# electrical_schematic.net
KiCad netlist of a schematic drawn in EAGLE
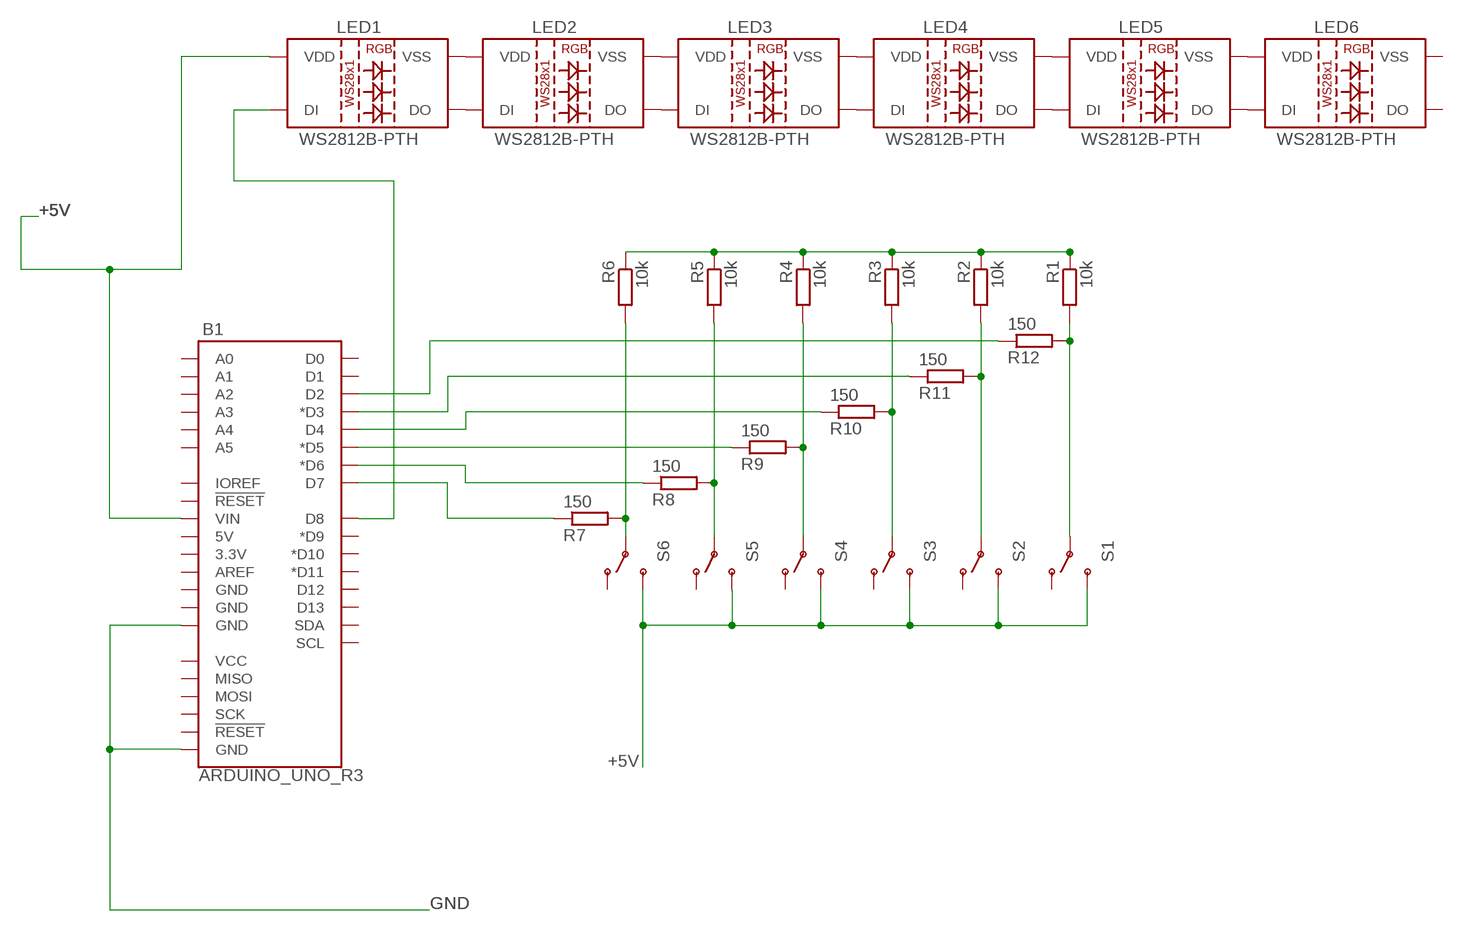
[diagram p0: schematic, sheet 1]

(export (version "E")
  (design (tool "Eeschema 10.0.6"))
  (components
    (comp (ref "B1")
      (value "ARDUINO_UNO_R3")
      (footprint "eagle-import:ARDUINO_R3")
      (libsource (lib "eagle-import") (part "ARDUINO_UNO_R3"))
    )
    (comp (ref "LED1")
      (value "WS2812B-PTH")
      (footprint "eagle-import:WS2812B-PTH-KIT")
      (libsource (lib "eagle-import") (part "WS2812B-PTH"))
    )
    (comp (ref "LED2")
      (value "WS2812B-PTH")
      (footprint "eagle-import:WS2812B-PTH-KIT")
      (libsource (lib "eagle-import") (part "WS2812B-PTH"))
    )
    (comp (ref "LED3")
      (value "WS2812B-PTH")
      (footprint "eagle-import:WS2812B-PTH-KIT")
      (libsource (lib "eagle-import") (part "WS2812B-PTH"))
    )
    (comp (ref "LED4")
      (value "WS2812B-PTH")
      (footprint "eagle-import:WS2812B-PTH-KIT")
      (libsource (lib "eagle-import") (part "WS2812B-PTH"))
    )
    (comp (ref "LED5")
      (value "WS2812B-PTH")
      (footprint "eagle-import:WS2812B-PTH-KIT")
      (libsource (lib "eagle-import") (part "WS2812B-PTH"))
    )
    (comp (ref "LED6")
      (value "WS2812B-PTH")
      (footprint "eagle-import:WS2812B-PTH-KIT")
      (libsource (lib "eagle-import") (part "WS2812B-PTH"))
    )
    (comp (ref "R1")
      (value "10k")
      (footprint "eagle-import:0207_12")
      (libsource (lib "eagle-import") (part "R-EU_0207/12"))
    )
    (comp (ref "R2")
      (value "10k")
      (footprint "eagle-import:0207_12")
      (libsource (lib "eagle-import") (part "R-EU_0207/12"))
    )
    (comp (ref "R3")
      (value "10k")
      (footprint "eagle-import:0207_12")
      (libsource (lib "eagle-import") (part "R-EU_0207/12"))
    )
    (comp (ref "R4")
      (value "10k")
      (footprint "eagle-import:0207_12")
      (libsource (lib "eagle-import") (part "R-EU_0207/12"))
    )
    (comp (ref "R5")
      (value "10k")
      (footprint "eagle-import:0207_12")
      (libsource (lib "eagle-import") (part "R-EU_0207/12"))
    )
    (comp (ref "R6")
      (value "10k")
      (footprint "eagle-import:0207_12")
      (libsource (lib "eagle-import") (part "R-EU_0207/12"))
    )
    (comp (ref "R7")
      (value "150")
      (footprint "eagle-import:0207_12")
      (libsource (lib "eagle-import") (part "R-EU_0207/12"))
    )
    (comp (ref "R8")
      (value "150")
      (footprint "eagle-import:0207_12")
      (libsource (lib "eagle-import") (part "R-EU_0207/12"))
    )
    (comp (ref "R9")
      (value "150")
      (footprint "eagle-import:0207_12")
      (libsource (lib "eagle-import") (part "R-EU_0207/12"))
    )
    (comp (ref "R10")
      (value "150")
      (footprint "eagle-import:0207_12")
      (libsource (lib "eagle-import") (part "R-EU_0207/12"))
    )
    (comp (ref "R11")
      (value "150")
      (footprint "eagle-import:0207_12")
      (libsource (lib "eagle-import") (part "R-EU_0207/12"))
    )
    (comp (ref "R12")
      (value "150")
      (footprint "eagle-import:0207_12")
      (libsource (lib "eagle-import") (part "R-EU_0207/12"))
    )
    (comp (ref "S1")
      (value "SWITCH-SPDTPTH3")
      (footprint "eagle-import:R_SW_TH")
      (libsource (lib "eagle-import") (part "SWITCH-SPDTPTH3"))
    )
    (comp (ref "S2")
      (value "SWITCH-SPDTPTH3")
      (footprint "eagle-import:R_SW_TH")
      (libsource (lib "eagle-import") (part "SWITCH-SPDTPTH3"))
    )
    (comp (ref "S3")
      (value "SWITCH-SPDTPTH3")
      (footprint "eagle-import:R_SW_TH")
      (libsource (lib "eagle-import") (part "SWITCH-SPDTPTH3"))
    )
    (comp (ref "S4")
      (value "SWITCH-SPDTPTH3")
      (footprint "eagle-import:R_SW_TH")
      (libsource (lib "eagle-import") (part "SWITCH-SPDTPTH3"))
    )
    (comp (ref "S5")
      (value "SWITCH-SPDTPTH3")
      (footprint "eagle-import:R_SW_TH")
      (libsource (lib "eagle-import") (part "SWITCH-SPDTPTH3"))
    )
    (comp (ref "S6")
      (value "SWITCH-SPDTPTH3")
      (footprint "eagle-import:R_SW_TH")
      (libsource (lib "eagle-import") (part "SWITCH-SPDTPTH3"))
    )
  )
  (nets
    (net (code "1") (name "/+5V") (class "Default")
      (node (ref "B1") (pin "VIN") (pinfunction "VIN_VIN") (pintype "bidirectional"))
      (node (ref "LED1") (pin "3") (pinfunction "VDD_3") (pintype "bidirectional"))
    )
    (net (code "2") (name "/GND") (class "Default")
      (node (ref "B1") (pin "GND@1") (pinfunction "GND_GND@1") (pintype "bidirectional"))
      (node (ref "B1") (pin "GND@2") (pinfunction "GND_GND@2") (pintype "bidirectional"))
    )
    (net (code "3") (name "Net-(B1-*D3)") (class "Default")
      (node (ref "B1") (pin "D3") (pinfunction "*D3_D3") (pintype "bidirectional"))
      (node (ref "R11") (pin "1") (pinfunction "1_1") (pintype "passive"))
    )
    (net (code "4") (name "Net-(B1-*D5)") (class "Default")
      (node (ref "B1") (pin "D5") (pinfunction "*D5_D5") (pintype "bidirectional"))
      (node (ref "R9") (pin "1") (pinfunction "1_1") (pintype "passive"))
    )
    (net (code "5") (name "Net-(B1-*D6)") (class "Default")
      (node (ref "B1") (pin "D6") (pinfunction "*D6_D6") (pintype "bidirectional"))
      (node (ref "R8") (pin "1") (pinfunction "1_1") (pintype "passive"))
    )
    (net (code "6") (name "Net-(B1-PadD2)") (class "Default")
      (node (ref "B1") (pin "D2") (pinfunction "D2_D2") (pintype "bidirectional"))
      (node (ref "R12") (pin "1") (pinfunction "1_1") (pintype "passive"))
    )
    (net (code "7") (name "Net-(B1-PadD4)") (class "Default")
      (node (ref "B1") (pin "D4") (pinfunction "D4_D4") (pintype "bidirectional"))
      (node (ref "R10") (pin "1") (pinfunction "1_1") (pintype "passive"))
    )
    (net (code "8") (name "Net-(B1-PadD7)") (class "Default")
      (node (ref "B1") (pin "D7") (pinfunction "D7_D7") (pintype "bidirectional"))
      (node (ref "R7") (pin "1") (pinfunction "1_1") (pintype "passive"))
    )
    (net (code "9") (name "Net-(LED1-DI)") (class "Default")
      (node (ref "B1") (pin "D8") (pinfunction "D8_D8") (pintype "bidirectional"))
      (node (ref "LED1") (pin "4") (pinfunction "DI_4") (pintype "bidirectional"))
    )
    (net (code "10") (name "Net-(LED1-DO)") (class "Default")
      (node (ref "LED1") (pin "1") (pinfunction "DO_1") (pintype "bidirectional"))
      (node (ref "LED2") (pin "4") (pinfunction "DI_4") (pintype "bidirectional"))
    )
    (net (code "11") (name "Net-(LED1-VSS)") (class "Default")
      (node (ref "LED1") (pin "2") (pinfunction "VSS_2") (pintype "bidirectional"))
      (node (ref "LED2") (pin "3") (pinfunction "VDD_3") (pintype "bidirectional"))
    )
    (net (code "12") (name "Net-(LED2-DO)") (class "Default")
      (node (ref "LED2") (pin "1") (pinfunction "DO_1") (pintype "bidirectional"))
      (node (ref "LED3") (pin "4") (pinfunction "DI_4") (pintype "bidirectional"))
    )
    (net (code "13") (name "Net-(LED2-VSS)") (class "Default")
      (node (ref "LED2") (pin "2") (pinfunction "VSS_2") (pintype "bidirectional"))
      (node (ref "LED3") (pin "3") (pinfunction "VDD_3") (pintype "bidirectional"))
    )
    (net (code "14") (name "Net-(LED3-DO)") (class "Default")
      (node (ref "LED3") (pin "1") (pinfunction "DO_1") (pintype "bidirectional"))
      (node (ref "LED4") (pin "4") (pinfunction "DI_4") (pintype "bidirectional"))
    )
    (net (code "15") (name "Net-(LED3-VSS)") (class "Default")
      (node (ref "LED3") (pin "2") (pinfunction "VSS_2") (pintype "bidirectional"))
      (node (ref "LED4") (pin "3") (pinfunction "VDD_3") (pintype "bidirectional"))
    )
    (net (code "16") (name "Net-(LED4-DO)") (class "Default")
      (node (ref "LED4") (pin "1") (pinfunction "DO_1") (pintype "bidirectional"))
      (node (ref "LED5") (pin "4") (pinfunction "DI_4") (pintype "bidirectional"))
    )
    (net (code "17") (name "Net-(LED4-VSS)") (class "Default")
      (node (ref "LED4") (pin "2") (pinfunction "VSS_2") (pintype "bidirectional"))
      (node (ref "LED5") (pin "3") (pinfunction "VDD_3") (pintype "bidirectional"))
    )
    (net (code "18") (name "Net-(LED5-DO)") (class "Default")
      (node (ref "LED5") (pin "1") (pinfunction "DO_1") (pintype "bidirectional"))
      (node (ref "LED6") (pin "4") (pinfunction "DI_4") (pintype "bidirectional"))
    )
    (net (code "19") (name "Net-(LED5-VSS)") (class "Default")
      (node (ref "LED5") (pin "2") (pinfunction "VSS_2") (pintype "bidirectional"))
      (node (ref "LED6") (pin "3") (pinfunction "VDD_3") (pintype "bidirectional"))
    )
    (net (code "20") (name "Net-(R1-Pad1)") (class "Default")
      (node (ref "R1") (pin "1") (pinfunction "1_1") (pintype "passive"))
      (node (ref "R2") (pin "1") (pinfunction "1_1") (pintype "passive"))
      (node (ref "R3") (pin "1") (pinfunction "1_1") (pintype "passive"))
      (node (ref "R4") (pin "1") (pinfunction "1_1") (pintype "passive"))
      (node (ref "R5") (pin "1") (pinfunction "1_1") (pintype "passive"))
      (node (ref "R6") (pin "1") (pinfunction "1_1") (pintype "passive"))
    )
    (net (code "21") (name "Net-(S1-P)") (class "Default")
      (node (ref "R1") (pin "2") (pinfunction "2_2") (pintype "passive"))
      (node (ref "R12") (pin "2") (pinfunction "2_2") (pintype "passive"))
      (node (ref "S1") (pin "P$2") (pinfunction "P_P$2") (pintype "passive"))
    )
    (net (code "22") (name "Net-(S1-S)") (class "Default")
      (node (ref "S1") (pin "P$3") (pinfunction "S_P$3") (pintype "passive"))
      (node (ref "S2") (pin "P$3") (pinfunction "S_P$3") (pintype "passive"))
      (node (ref "S3") (pin "P$3") (pinfunction "S_P$3") (pintype "passive"))
      (node (ref "S4") (pin "P$3") (pinfunction "S_P$3") (pintype "passive"))
      (node (ref "S5") (pin "P$3") (pinfunction "S_P$3") (pintype "passive"))
      (node (ref "S6") (pin "P$3") (pinfunction "S_P$3") (pintype "passive"))
    )
    (net (code "23") (name "Net-(S2-P)") (class "Default")
      (node (ref "R11") (pin "2") (pinfunction "2_2") (pintype "passive"))
      (node (ref "R2") (pin "2") (pinfunction "2_2") (pintype "passive"))
      (node (ref "S2") (pin "P$2") (pinfunction "P_P$2") (pintype "passive"))
    )
    (net (code "24") (name "Net-(S3-P)") (class "Default")
      (node (ref "R10") (pin "2") (pinfunction "2_2") (pintype "passive"))
      (node (ref "R3") (pin "2") (pinfunction "2_2") (pintype "passive"))
      (node (ref "S3") (pin "P$2") (pinfunction "P_P$2") (pintype "passive"))
    )
    (net (code "25") (name "Net-(S4-P)") (class "Default")
      (node (ref "R4") (pin "2") (pinfunction "2_2") (pintype "passive"))
      (node (ref "R9") (pin "2") (pinfunction "2_2") (pintype "passive"))
      (node (ref "S4") (pin "P$2") (pinfunction "P_P$2") (pintype "passive"))
    )
    (net (code "26") (name "Net-(S5-P)") (class "Default")
      (node (ref "R5") (pin "2") (pinfunction "2_2") (pintype "passive"))
      (node (ref "R8") (pin "2") (pinfunction "2_2") (pintype "passive"))
      (node (ref "S5") (pin "P$2") (pinfunction "P_P$2") (pintype "passive"))
    )
    (net (code "27") (name "Net-(S6-P)") (class "Default")
      (node (ref "R6") (pin "2") (pinfunction "2_2") (pintype "passive"))
      (node (ref "R7") (pin "2") (pinfunction "2_2") (pintype "passive"))
      (node (ref "S6") (pin "P$2") (pinfunction "P_P$2") (pintype "passive"))
    )
    (net (code "28") (name "unconnected-(B1-*D9-PadD9)") (class "Default")
      (node (ref "B1") (pin "D9") (pinfunction "*D9_D9") (pintype "bidirectional"))
    )
    (net (code "29") (name "unconnected-(B1-*D10-PadD10)") (class "Default")
      (node (ref "B1") (pin "D10") (pinfunction "*D10_D10") (pintype "bidirectional"))
    )
    (net (code "30") (name "unconnected-(B1-*D11-PadD11)") (class "Default")
      (node (ref "B1") (pin "D11") (pinfunction "*D11_D11") (pintype "bidirectional"))
    )
    (net (code "31") (name "unconnected-(B1-GND-PadGND@3)") (class "Default")
      (node (ref "B1") (pin "GND@3") (pinfunction "GND_GND@3") (pintype "bidirectional"))
    )
    (net (code "32") (name "unconnected-(B1-GND-PadGND@4)") (class "Default")
      (node (ref "B1") (pin "GND@4") (pinfunction "GND_GND@4") (pintype "bidirectional"))
    )
    (net (code "33") (name "unconnected-(B1-Pad3.3V)") (class "Default")
      (node (ref "B1") (pin "3.3V") (pinfunction "3.3V_3.3V") (pintype "bidirectional"))
    )
    (net (code "34") (name "unconnected-(B1-Pad5V)") (class "Default")
      (node (ref "B1") (pin "5V") (pinfunction "5V_5V") (pintype "bidirectional"))
    )
    (net (code "35") (name "unconnected-(B1-PadA0)") (class "Default")
      (node (ref "B1") (pin "A0") (pinfunction "A0_A0") (pintype "bidirectional"))
    )
    (net (code "36") (name "unconnected-(B1-PadA1)") (class "Default")
      (node (ref "B1") (pin "A1") (pinfunction "A1_A1") (pintype "bidirectional"))
    )
    (net (code "37") (name "unconnected-(B1-PadA2)") (class "Default")
      (node (ref "B1") (pin "A2") (pinfunction "A2_A2") (pintype "bidirectional"))
    )
    (net (code "38") (name "unconnected-(B1-PadA3)") (class "Default")
      (node (ref "B1") (pin "A3") (pinfunction "A3_A3") (pintype "bidirectional"))
    )
    (net (code "39") (name "unconnected-(B1-PadA4)") (class "Default")
      (node (ref "B1") (pin "A4") (pinfunction "A4_A4") (pintype "bidirectional"))
    )
    (net (code "40") (name "unconnected-(B1-PadA5)") (class "Default")
      (node (ref "B1") (pin "A5") (pinfunction "A5_A5") (pintype "bidirectional"))
    )
    (net (code "41") (name "unconnected-(B1-PadAREF)") (class "Default")
      (node (ref "B1") (pin "AREF") (pinfunction "AREF_AREF") (pintype "bidirectional"))
    )
    (net (code "42") (name "unconnected-(B1-PadD0)") (class "Default")
      (node (ref "B1") (pin "D0") (pinfunction "D0_D0") (pintype "bidirectional"))
    )
    (net (code "43") (name "unconnected-(B1-PadD1)") (class "Default")
      (node (ref "B1") (pin "D1") (pinfunction "D1_D1") (pintype "bidirectional"))
    )
    (net (code "44") (name "unconnected-(B1-PadD12)") (class "Default")
      (node (ref "B1") (pin "D12") (pinfunction "D12_D12") (pintype "bidirectional"))
    )
    (net (code "45") (name "unconnected-(B1-PadD13)") (class "Default")
      (node (ref "B1") (pin "D13") (pinfunction "D13_D13") (pintype "bidirectional"))
    )
    (net (code "46") (name "unconnected-(B1-PadIOREF)") (class "Default")
      (node (ref "B1") (pin "IOREF") (pinfunction "IOREF_IOREF") (pintype "bidirectional"))
    )
    (net (code "47") (name "unconnected-(B1-PadMISO)") (class "Default")
      (node (ref "B1") (pin "MISO") (pinfunction "MISO_MISO") (pintype "bidirectional"))
    )
    (net (code "48") (name "unconnected-(B1-PadMOSI)") (class "Default")
      (node (ref "B1") (pin "MOSI") (pinfunction "MOSI_MOSI") (pintype "bidirectional"))
    )
    (net (code "49") (name "unconnected-(B1-PadSCK)") (class "Default")
      (node (ref "B1") (pin "SCK") (pinfunction "SCK_SCK") (pintype "bidirectional"))
    )
    (net (code "50") (name "unconnected-(B1-PadSCL)") (class "Default")
      (node (ref "B1") (pin "SCL") (pinfunction "SCL_SCL") (pintype "bidirectional"))
    )
    (net (code "51") (name "unconnected-(B1-PadSDA)") (class "Default")
      (node (ref "B1") (pin "SDA") (pinfunction "SDA_SDA") (pintype "bidirectional"))
    )
    (net (code "52") (name "unconnected-(B1-PadVCC)") (class "Default")
      (node (ref "B1") (pin "VCC") (pinfunction "VCC_VCC") (pintype "bidirectional"))
    )
    (net (code "53") (name "unconnected-(B1-~{RESET}-PadRESET@1)") (class "Default")
      (node (ref "B1") (pin "RESET@1") (pinfunction "~{RESET}_RESET@1") (pintype "bidirectional"))
    )
    (net (code "54") (name "unconnected-(B1-~{RESET}-PadRESET@2)") (class "Default")
      (node (ref "B1") (pin "RESET@2") (pinfunction "~{RESET}_RESET@2") (pintype "bidirectional"))
    )
    (net (code "55") (name "unconnected-(LED6-DO-Pad1)") (class "Default")
      (node (ref "LED6") (pin "1") (pinfunction "DO_1") (pintype "bidirectional"))
    )
    (net (code "56") (name "unconnected-(LED6-VSS-Pad2)") (class "Default")
      (node (ref "LED6") (pin "2") (pinfunction "VSS_2") (pintype "bidirectional"))
    )
    (net (code "57") (name "unconnected-(S1-O-PadP$1)") (class "Default")
      (node (ref "S1") (pin "P$1") (pinfunction "O_P$1") (pintype "passive"))
    )
    (net (code "58") (name "unconnected-(S2-O-PadP$1)") (class "Default")
      (node (ref "S2") (pin "P$1") (pinfunction "O_P$1") (pintype "passive"))
    )
    (net (code "59") (name "unconnected-(S3-O-PadP$1)") (class "Default")
      (node (ref "S3") (pin "P$1") (pinfunction "O_P$1") (pintype "passive"))
    )
    (net (code "60") (name "unconnected-(S4-O-PadP$1)") (class "Default")
      (node (ref "S4") (pin "P$1") (pinfunction "O_P$1") (pintype "passive"))
    )
    (net (code "61") (name "unconnected-(S5-O-PadP$1)") (class "Default")
      (node (ref "S5") (pin "P$1") (pinfunction "O_P$1") (pintype "passive"))
    )
    (net (code "62") (name "unconnected-(S6-O-PadP$1)") (class "Default")
      (node (ref "S6") (pin "P$1") (pinfunction "O_P$1") (pintype "passive"))
    )
  )
)
